# CAN.net
KiCad netlist of a schematic drawn in Altium Designer
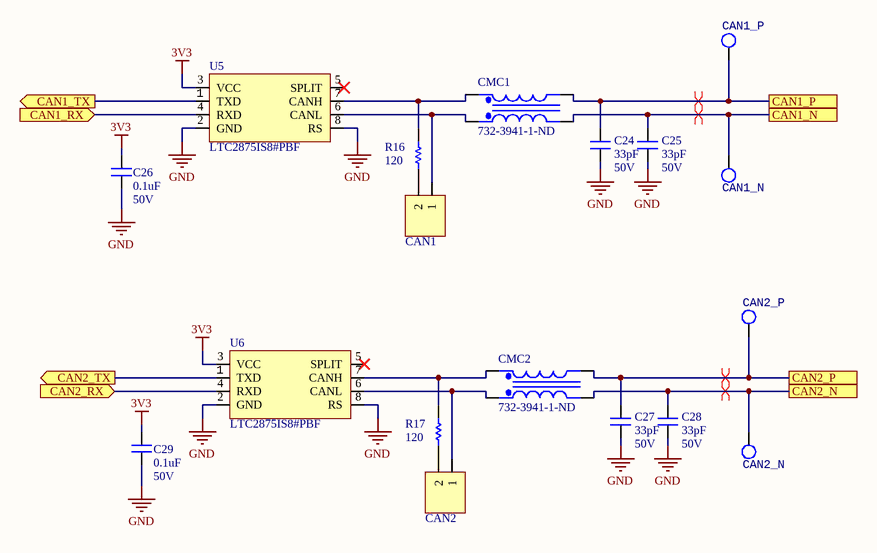
[diagram p0: CAN.SchDoc]

(export (version "E")
  (design (tool "Eeschema 10.0.6"))
  (components
    (comp (ref "C24")
      (value "CAP_33pF_50V_0603")
      (footprint "CAPC0603(1608)55_N")
      (description "CAP CER 33PF 50V C0G/NP0")
      (fields
        (field (name "VOLTAGE") "50V")
        (field (name "TOLERANCE") "5%")
        (field (name "CAPACITANCE") "33pF")
      )
      (libsource (lib "UWRT_Schematic_Library_2020") (part "CAP_33pF_50V_0603"))
    )
    (comp (ref "C25")
      (value "CAP_33pF_50V_0603")
      (footprint "CAPC0603(1608)55_N")
      (description "CAP CER 33PF 50V C0G/NP0")
      (fields
        (field (name "VOLTAGE") "50V")
        (field (name "TOLERANCE") "5%")
        (field (name "CAPACITANCE") "33pF")
      )
      (libsource (lib "UWRT_Schematic_Library_2020") (part "CAP_33pF_50V_0603"))
    )
    (comp (ref "C26")
      (value "0.1uF")
      (footprint "CAPC2012X140N")
      (description "CAP CER 0.1UF 50V X7R 0805")
      (fields
        (field (name "TOLERANCE") "10%")
        (field (name "VOLTAGE RATING") "50V")
        (field (name "Comment") "CAP_0.1uF_50V_0805")
      )
      (libsource (lib "UWRT_Schematic_Library_2020") (part "CAP_0.1uF_50V_0805"))
    )
    (comp (ref "C27")
      (value "CAP_33pF_50V_0603")
      (footprint "CAPC0603(1608)55_N")
      (description "CAP CER 33PF 50V C0G/NP0")
      (fields
        (field (name "VOLTAGE") "50V")
        (field (name "TOLERANCE") "5%")
        (field (name "CAPACITANCE") "33pF")
      )
      (libsource (lib "UWRT_Schematic_Library_2020") (part "CAP_33pF_50V_0603"))
    )
    (comp (ref "C28")
      (value "CAP_33pF_50V_0603")
      (footprint "CAPC0603(1608)55_N")
      (description "CAP CER 33PF 50V C0G/NP0")
      (fields
        (field (name "VOLTAGE") "50V")
        (field (name "TOLERANCE") "5%")
        (field (name "CAPACITANCE") "33pF")
      )
      (libsource (lib "UWRT_Schematic_Library_2020") (part "CAP_33pF_50V_0603"))
    )
    (comp (ref "C29")
      (value "0.1uF")
      (footprint "CAPC2012X140N")
      (description "CAP CER 0.1UF 50V X7R 0805")
      (fields
        (field (name "TOLERANCE") "10%")
        (field (name "VOLTAGE RATING") "50V")
        (field (name "Comment") "CAP_0.1uF_50V_0805")
      )
      (libsource (lib "UWRT_Schematic_Library_2020") (part "CAP_0.1uF_50V_0805"))
    )
    (comp (ref "CAN1")
      (value "JUMPER_2")
      (footprint "HDR1X2")
      (description "HEADER 2X1")
      (libsource (lib "UWRT_Schematic_Library_2020") (part "JUMPER_2"))
    )
    (comp (ref "CAN1_N")
      (value "TESTPOINT_LOOP")
      (footprint "TESTPOINT_LOOP")
      (description "Loop testpoint through-hole pad")
      (libsource (lib "UWRT_Schematic_Library_2020") (part "TESTPOINT_LOOP"))
    )
    (comp (ref "CAN1_P")
      (value "TESTPOINT_LOOP")
      (footprint "TESTPOINT_LOOP")
      (description "Loop testpoint through-hole pad")
      (libsource (lib "UWRT_Schematic_Library_2020") (part "TESTPOINT_LOOP"))
    )
    (comp (ref "CAN2")
      (value "JUMPER_2")
      (footprint "HDR1X2")
      (description "HEADER 2X1")
      (libsource (lib "UWRT_Schematic_Library_2020") (part "JUMPER_2"))
    )
    (comp (ref "CAN2_N")
      (value "TESTPOINT_LOOP")
      (footprint "TESTPOINT_LOOP")
      (description "Loop testpoint through-hole pad")
      (libsource (lib "UWRT_Schematic_Library_2020") (part "TESTPOINT_LOOP"))
    )
    (comp (ref "CAN2_P")
      (value "TESTPOINT_LOOP")
      (footprint "TESTPOINT_LOOP")
      (description "Loop testpoint through-hole pad")
      (libsource (lib "UWRT_Schematic_Library_2020") (part "TESTPOINT_LOOP"))
    )
    (comp (ref "CMC1")
      (value "CMC_51uH")
      (footprint "744212510")
      (description "CMC 51uH 300MA 2LN SMD")
      (fields (field (name "TOLERANCE") "50%") (field (name "SUPPLIER PART NUMBER 1") "732-3941-1-ND"))
      (libsource (lib "UWRT_Schematic_Library_2020") (part "CMC_51uH"))
    )
    (comp (ref "CMC2")
      (value "CMC_51uH")
      (footprint "744212510")
      (description "CMC 51uH 300MA 2LN SMD")
      (fields (field (name "TOLERANCE") "50%") (field (name "SUPPLIER PART NUMBER 1") "732-3941-1-ND"))
      (libsource (lib "UWRT_Schematic_Library_2020") (part "CMC_51uH"))
    )
    (comp (ref "R16")
      (value "120")
      (footprint "RESC0603(1608)_N")
      (description "RES SMD 120 OHM 5% 1/10W 0603")
      (fields (field (name "TOLERANCE") "5%") (field (name "Comment") "RES_120R_0603"))
      (libsource (lib "UWRT_Schematic_Library_2020") (part "RES_120R_0603"))
    )
    (comp (ref "R17")
      (value "120")
      (footprint "RESC0603(1608)_N")
      (description "RES SMD 120 OHM 5% 1/10W 0603")
      (fields (field (name "TOLERANCE") "5%") (field (name "Comment") "RES_120R_0603"))
      (libsource (lib "UWRT_Schematic_Library_2020") (part "RES_120R_0603"))
    )
    (comp (ref "U5")
      (value "IC TXRX CAN")
      (footprint "LT-S8_N")
      (description "IC TXRX CAN 4MBPS 8SO")
      (fields (field (name "MANUFACTURER PART NUMBER 1") "LTC2875IS8#PBF"))
      (libsource (lib "UWRT_Schematic_Library_2020") (part "LTC2875"))
    )
    (comp (ref "U6")
      (value "IC TXRX CAN")
      (footprint "LT-S8_N")
      (description "IC TXRX CAN 4MBPS 8SO")
      (fields (field (name "MANUFACTURER PART NUMBER 1") "LTC2875IS8#PBF"))
      (libsource (lib "UWRT_Schematic_Library_2020") (part "LTC2875"))
    )
  )
  (nets
    (net (code "1") (name "/CAN1_N") (class "Default")
      (node (ref "C25") (pin "2") (pinfunction "2_2") (pintype "passive"))
      (node (ref "CAN1_N") (pin "1") (pintype "passive"))
      (node (ref "CMC1") (pin "5") (pinfunction "Pri-_5") (pintype "passive"))
    )
    (net (code "2") (name "/CAN1_P") (class "Default")
      (node (ref "C24") (pin "2") (pinfunction "2_2") (pintype "passive"))
      (node (ref "CAN1_P") (pin "1") (pintype "passive"))
      (node (ref "CMC1") (pin "4") (pinfunction "Sec-_4") (pintype "passive"))
    )
    (net (code "3") (name "/CAN1_RX") (class "Default")
      (node (ref "U5") (pin "4") (pinfunction "RXD_4") (pintype "passive"))
    )
    (net (code "4") (name "/CAN1_TX") (class "Default")
      (node (ref "U5") (pin "1") (pinfunction "TXD_1") (pintype "passive"))
    )
    (net (code "5") (name "/CAN2_N") (class "Default")
      (node (ref "C28") (pin "2") (pinfunction "2_2") (pintype "passive"))
      (node (ref "CAN2_N") (pin "1") (pintype "passive"))
      (node (ref "CMC2") (pin "5") (pinfunction "Pri-_5") (pintype "passive"))
    )
    (net (code "6") (name "/CAN2_P") (class "Default")
      (node (ref "C27") (pin "2") (pinfunction "2_2") (pintype "passive"))
      (node (ref "CAN2_P") (pin "1") (pintype "passive"))
      (node (ref "CMC2") (pin "4") (pinfunction "Sec-_4") (pintype "passive"))
    )
    (net (code "7") (name "/CAN2_RX") (class "Default")
      (node (ref "U6") (pin "4") (pinfunction "RXD_4") (pintype "passive"))
    )
    (net (code "8") (name "/CAN2_TX") (class "Default")
      (node (ref "U6") (pin "1") (pinfunction "TXD_1") (pintype "passive"))
    )
    (net (code "9") (name "3V3") (class "Default")
      (node (ref "C26") (pin "2") (pinfunction "2_2") (pintype "passive"))
      (node (ref "C29") (pin "2") (pinfunction "2_2") (pintype "passive"))
      (node (ref "U5") (pin "3") (pinfunction "VCC_3") (pintype "passive"))
      (node (ref "U6") (pin "3") (pinfunction "VCC_3") (pintype "passive"))
    )
    (net (code "10") (name "GND") (class "Default")
      (node (ref "C24") (pin "1") (pinfunction "1_1") (pintype "passive"))
      (node (ref "C25") (pin "1") (pinfunction "1_1") (pintype "passive"))
      (node (ref "C26") (pin "1") (pinfunction "1_1") (pintype "passive"))
      (node (ref "C27") (pin "1") (pinfunction "1_1") (pintype "passive"))
      (node (ref "C28") (pin "1") (pinfunction "1_1") (pintype "passive"))
      (node (ref "C29") (pin "1") (pinfunction "1_1") (pintype "passive"))
      (node (ref "U5") (pin "2") (pinfunction "GND_2") (pintype "passive"))
      (node (ref "U5") (pin "8") (pinfunction "RS_8") (pintype "passive"))
      (node (ref "U6") (pin "2") (pinfunction "GND_2") (pintype "passive"))
      (node (ref "U6") (pin "8") (pinfunction "RS_8") (pintype "passive"))
    )
    (net (code "11") (name "Net-(CAN1-Pad2)") (class "Default")
      (node (ref "CAN1") (pin "2") (pinfunction "2_2") (pintype "passive"))
      (node (ref "R16") (pin "2") (pinfunction "2_2") (pintype "passive"))
    )
    (net (code "12") (name "Net-(CAN2-Pad2)") (class "Default")
      (node (ref "CAN2") (pin "2") (pinfunction "2_2") (pintype "passive"))
      (node (ref "R17") (pin "2") (pinfunction "2_2") (pintype "passive"))
    )
    (net (code "13") (name "Net-(CMC1-Pri+)") (class "Default")
      (node (ref "CAN1") (pin "1") (pinfunction "1_1") (pintype "passive"))
      (node (ref "CMC1") (pin "1") (pinfunction "Pri+_1") (pintype "passive"))
      (node (ref "U5") (pin "6") (pinfunction "CANL_6") (pintype "passive"))
    )
    (net (code "14") (name "Net-(CMC1-Sec+)") (class "Default")
      (node (ref "CMC1") (pin "3") (pinfunction "Sec+_3") (pintype "passive"))
      (node (ref "R16") (pin "1") (pinfunction "1_1") (pintype "passive"))
      (node (ref "U5") (pin "7") (pinfunction "CANH_7") (pintype "passive"))
    )
    (net (code "15") (name "Net-(CMC2-Pri+)") (class "Default")
      (node (ref "CAN2") (pin "1") (pinfunction "1_1") (pintype "passive"))
      (node (ref "CMC2") (pin "1") (pinfunction "Pri+_1") (pintype "passive"))
      (node (ref "U6") (pin "6") (pinfunction "CANL_6") (pintype "passive"))
    )
    (net (code "16") (name "Net-(CMC2-Sec+)") (class "Default")
      (node (ref "CMC2") (pin "3") (pinfunction "Sec+_3") (pintype "passive"))
      (node (ref "R17") (pin "1") (pinfunction "1_1") (pintype "passive"))
      (node (ref "U6") (pin "7") (pinfunction "CANH_7") (pintype "passive"))
    )
    (net (code "17") (name "unconnected-(U5-SPLIT-Pad5)") (class "Default")
      (node (ref "U5") (pin "5") (pinfunction "SPLIT_5") (pintype "passive+no_connect"))
    )
    (net (code "18") (name "unconnected-(U6-SPLIT-Pad5)") (class "Default")
      (node (ref "U6") (pin "5") (pinfunction "SPLIT_5") (pintype "passive+no_connect"))
    )
  )
)
